# SCH_wifi-temp-sensor_2024-08-15.net
KiCad netlist of a schematic drawn in EasyEDA
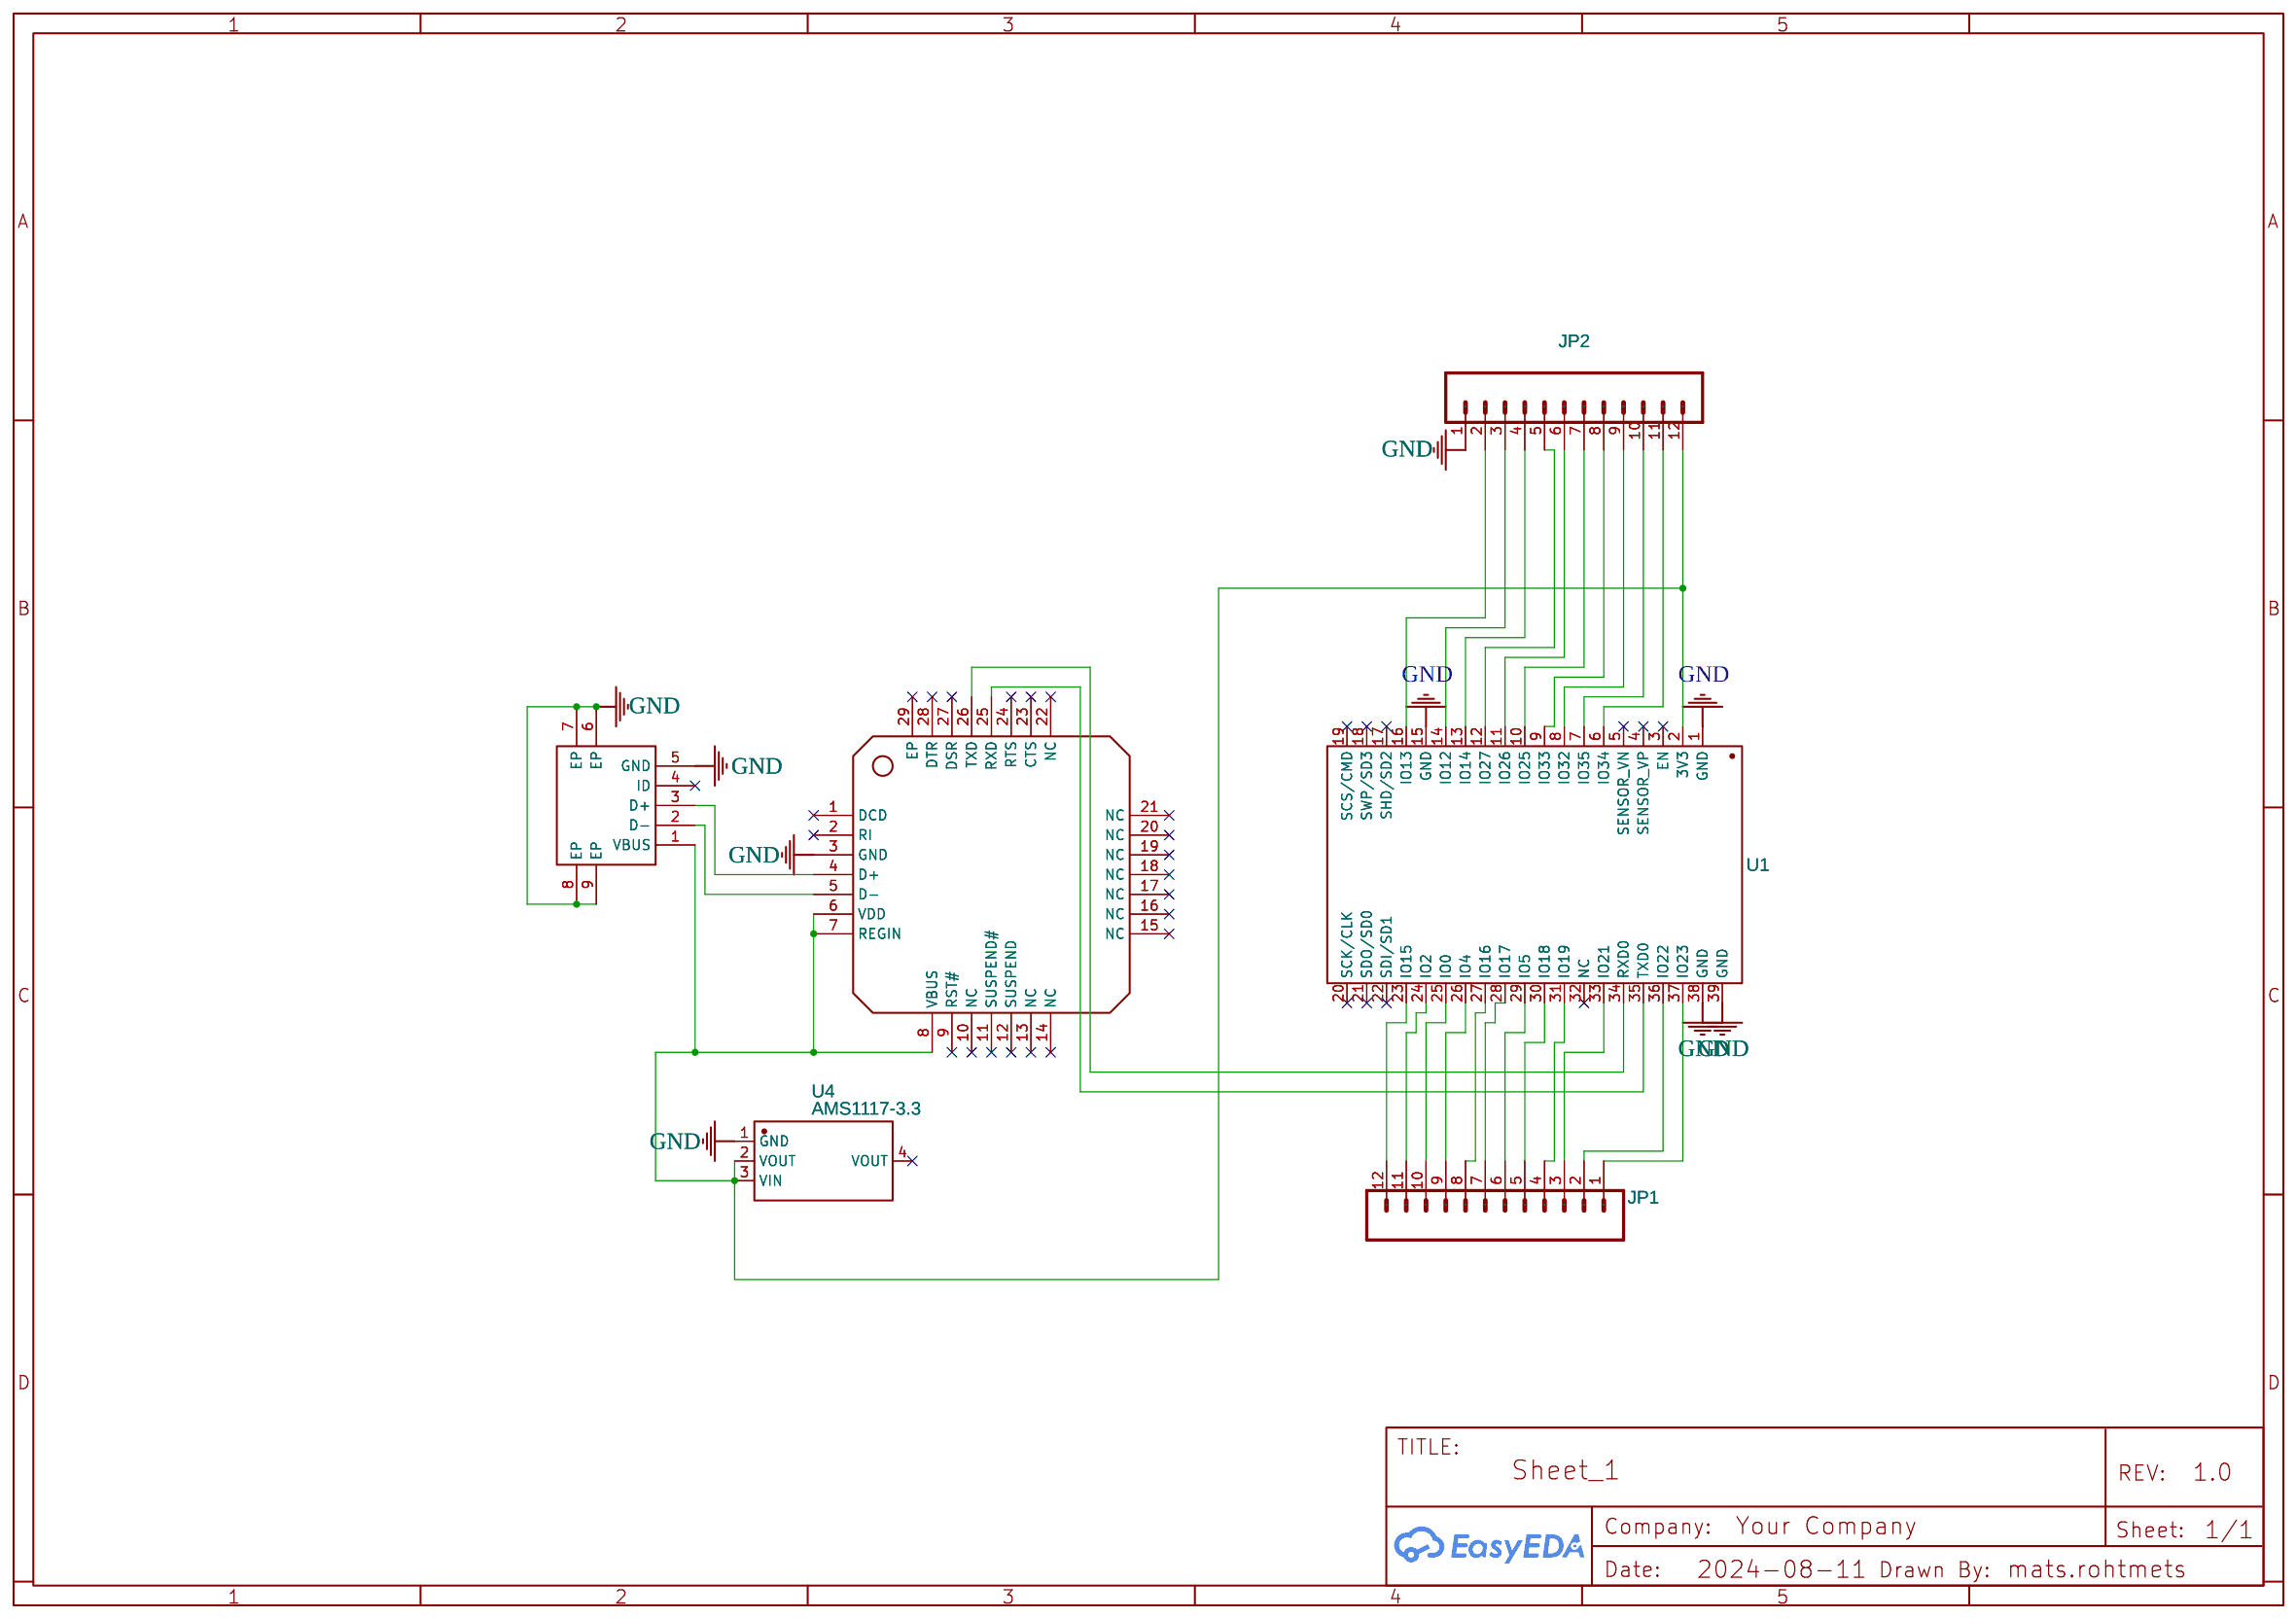
[diagram p0: schematic sheet]

(export (version "E")
  (design (tool "Eeschema 10.0.6"))
  (components
    (comp (ref "JP1")
      (value "M12MACHINE-PIN_LOCK")
      (fields
        (field (name "Manufacturer Part") "HC-PM254-8.5H-1x12PZ")
        (field (name "Manufacturer") "Hong Cheng")
      )
      (libsource (lib "") (part "M12MACHINE-PIN_LOCK"))
    )
    (comp (ref "JP2")
      (value "M12MACHINE-PIN_LOCK")
      (fields
        (field (name "Manufacturer Part") "HC-PM254-8.5H-1x12PZ")
        (field (name "Manufacturer") "Hong Cheng")
      )
      (libsource (lib "") (part "M12MACHINE-PIN_LOCK_1"))
    )
    (comp (ref "U1")
      (value "ESP32-WROOM-32")
      (fields
        (field (name "Manufacturer Part") "ESP32-WROOM-32-N4")
        (field (name "Manufacturer") "ESPRESSIF(乐鑫)")
      )
      (libsource (lib "") (part "ESP32-WROOM-32"))
    )
    (comp (ref "U3")
      (value "CP2102-GMR")
      (fields (field (name "Manufacturer") "SKYWORKS/SILICON LABS(芯科)"))
      (libsource (lib "") (part "CP2102-GMR"))
    )
    (comp (ref "U4")
      (value "AMS1117-3.3")
      (fields (field (name "Manufacturer") "AMS"))
      (libsource (lib "") (part "AMS1117-3.3"))
    )
    (comp (ref "USB1")
      (value "MICRO 7.2JB")
      (fields (field (name "Manufacturer") "SHOU HAN(首韩)"))
      (libsource (lib "") (part "MICRO 7.2JB"))
    )
  )
  (nets
    (net (code "1") (name "GND") (class "Default")
      (node (ref "JP2") (pin "1") (pinfunction "1_1") (pintype "bidirectional"))
      (node (ref "U1") (pin "1") (pinfunction "GND_1") (pintype "unspecified"))
      (node (ref "U1") (pin "15") (pinfunction "GND_15") (pintype "unspecified"))
      (node (ref "U1") (pin "38") (pinfunction "GND_38") (pintype "unspecified"))
      (node (ref "U1") (pin "39") (pinfunction "GND_39") (pintype "unspecified"))
      (node (ref "U3") (pin "3") (pinfunction "GND_3") (pintype "unspecified"))
      (node (ref "U4") (pin "1") (pinfunction "GND_1") (pintype "unspecified"))
      (node (ref "USB1") (pin "5") (pinfunction "GND_5") (pintype "unspecified"))
      (node (ref "USB1") (pin "6") (pinfunction "EP_6") (pintype "unspecified"))
      (node (ref "USB1") (pin "7") (pinfunction "EP_7") (pintype "unspecified"))
      (node (ref "USB1") (pin "8") (pinfunction "EP_8") (pintype "unspecified"))
      (node (ref "USB1") (pin "9") (pinfunction "EP_9") (pintype "unspecified"))
    )
    (net (code "2") (name "Net-(U1-3V3)") (class "Default")
      (node (ref "JP2") (pin "12") (pinfunction "12_12") (pintype "bidirectional"))
      (node (ref "U1") (pin "2") (pinfunction "3V3_2") (pintype "unspecified"))
      (node (ref "U3") (pin "6") (pinfunction "VDD_6") (pintype "unspecified"))
      (node (ref "U3") (pin "7") (pinfunction "REGIN_7") (pintype "unspecified"))
      (node (ref "U3") (pin "8") (pinfunction "VBUS_8") (pintype "unspecified"))
      (node (ref "U4") (pin "2") (pinfunction "VOUT_2") (pintype "unspecified"))
      (node (ref "U4") (pin "3") (pinfunction "VIN_3") (pintype "unspecified"))
      (node (ref "USB1") (pin "1") (pinfunction "VBUS_1") (pintype "unspecified"))
    )
    (net (code "3") (name "Net-(U1-IO0)") (class "Default")
      (node (ref "JP1") (pin "10") (pinfunction "10_10") (pintype "bidirectional"))
      (node (ref "U1") (pin "25") (pinfunction "IO0_25") (pintype "unspecified"))
    )
    (net (code "4") (name "Net-(U1-IO2)") (class "Default")
      (node (ref "JP1") (pin "11") (pinfunction "11_11") (pintype "bidirectional"))
      (node (ref "U1") (pin "24") (pinfunction "IO2_24") (pintype "unspecified"))
    )
    (net (code "5") (name "Net-(U1-IO4)") (class "Default")
      (node (ref "JP1") (pin "9") (pinfunction "9_9") (pintype "bidirectional"))
      (node (ref "U1") (pin "26") (pinfunction "IO4_26") (pintype "unspecified"))
    )
    (net (code "6") (name "Net-(U1-IO5)") (class "Default")
      (node (ref "JP1") (pin "6") (pinfunction "6_6") (pintype "bidirectional"))
      (node (ref "U1") (pin "29") (pinfunction "IO5_29") (pintype "unspecified"))
    )
    (net (code "7") (name "Net-(U1-IO12)") (class "Default")
      (node (ref "JP2") (pin "3") (pinfunction "3_3") (pintype "bidirectional"))
      (node (ref "U1") (pin "14") (pinfunction "IO12_14") (pintype "unspecified"))
    )
    (net (code "8") (name "Net-(U1-IO13)") (class "Default")
      (node (ref "JP2") (pin "2") (pinfunction "2_2") (pintype "bidirectional"))
      (node (ref "U1") (pin "16") (pinfunction "IO13_16") (pintype "unspecified"))
    )
    (net (code "9") (name "Net-(U1-IO14)") (class "Default")
      (node (ref "JP2") (pin "4") (pinfunction "4_4") (pintype "bidirectional"))
      (node (ref "U1") (pin "13") (pinfunction "IO14_13") (pintype "unspecified"))
    )
    (net (code "10") (name "Net-(U1-IO15)") (class "Default")
      (node (ref "JP1") (pin "12") (pinfunction "12_12") (pintype "bidirectional"))
      (node (ref "U1") (pin "23") (pinfunction "IO15_23") (pintype "unspecified"))
    )
    (net (code "11") (name "Net-(U1-IO16)") (class "Default")
      (node (ref "JP1") (pin "8") (pinfunction "8_8") (pintype "bidirectional"))
      (node (ref "U1") (pin "27") (pinfunction "IO16_27") (pintype "unspecified"))
    )
    (net (code "12") (name "Net-(U1-IO17)") (class "Default")
      (node (ref "JP1") (pin "7") (pinfunction "7_7") (pintype "bidirectional"))
      (node (ref "U1") (pin "28") (pinfunction "IO17_28") (pintype "unspecified"))
    )
    (net (code "13") (name "Net-(U1-IO18)") (class "Default")
      (node (ref "JP1") (pin "5") (pinfunction "5_5") (pintype "bidirectional"))
      (node (ref "U1") (pin "30") (pinfunction "IO18_30") (pintype "unspecified"))
    )
    (net (code "14") (name "Net-(U1-IO19)") (class "Default")
      (node (ref "JP1") (pin "4") (pinfunction "4_4") (pintype "bidirectional"))
      (node (ref "U1") (pin "31") (pinfunction "IO19_31") (pintype "unspecified"))
    )
    (net (code "15") (name "Net-(U1-IO21)") (class "Default")
      (node (ref "JP1") (pin "3") (pinfunction "3_3") (pintype "bidirectional"))
      (node (ref "U1") (pin "33") (pinfunction "IO21_33") (pintype "unspecified"))
    )
    (net (code "16") (name "Net-(U1-IO22)") (class "Default")
      (node (ref "JP1") (pin "2") (pinfunction "2_2") (pintype "bidirectional"))
      (node (ref "U1") (pin "36") (pinfunction "IO22_36") (pintype "unspecified"))
    )
    (net (code "17") (name "Net-(U1-IO23)") (class "Default")
      (node (ref "JP1") (pin "1") (pinfunction "1_1") (pintype "bidirectional"))
      (node (ref "U1") (pin "37") (pinfunction "IO23_37") (pintype "unspecified"))
    )
    (net (code "18") (name "Net-(U1-IO25)") (class "Default")
      (node (ref "JP2") (pin "7") (pinfunction "7_7") (pintype "bidirectional"))
      (node (ref "U1") (pin "10") (pinfunction "IO25_10") (pintype "unspecified"))
    )
    (net (code "19") (name "Net-(U1-IO26)") (class "Default")
      (node (ref "JP2") (pin "6") (pinfunction "6_6") (pintype "bidirectional"))
      (node (ref "U1") (pin "11") (pinfunction "IO26_11") (pintype "unspecified"))
    )
    (net (code "20") (name "Net-(U1-IO27)") (class "Default")
      (node (ref "JP2") (pin "5") (pinfunction "5_5") (pintype "bidirectional"))
      (node (ref "U1") (pin "12") (pinfunction "IO27_12") (pintype "unspecified"))
    )
    (net (code "21") (name "Net-(U1-IO32)") (class "Default")
      (node (ref "JP2") (pin "9") (pinfunction "9_9") (pintype "bidirectional"))
      (node (ref "U1") (pin "8") (pinfunction "IO32_8") (pintype "unspecified"))
    )
    (net (code "22") (name "Net-(U1-IO33)") (class "Default")
      (node (ref "JP2") (pin "8") (pinfunction "8_8") (pintype "bidirectional"))
      (node (ref "U1") (pin "9") (pinfunction "IO33_9") (pintype "unspecified"))
    )
    (net (code "23") (name "Net-(U1-IO34)") (class "Default")
      (node (ref "JP2") (pin "11") (pinfunction "11_11") (pintype "bidirectional"))
      (node (ref "U1") (pin "6") (pinfunction "IO34_6") (pintype "unspecified"))
    )
    (net (code "24") (name "Net-(U1-IO35)") (class "Default")
      (node (ref "JP2") (pin "10") (pinfunction "10_10") (pintype "bidirectional"))
      (node (ref "U1") (pin "7") (pinfunction "IO35_7") (pintype "unspecified"))
    )
    (net (code "25") (name "Net-(U1-RXD0)") (class "Default")
      (node (ref "U1") (pin "34") (pinfunction "RXD0_34") (pintype "unspecified"))
      (node (ref "U3") (pin "26") (pinfunction "TXD_26") (pintype "unspecified"))
    )
    (net (code "26") (name "Net-(U1-TXD0)") (class "Default")
      (node (ref "U1") (pin "35") (pinfunction "TXD0_35") (pintype "unspecified"))
      (node (ref "U3") (pin "25") (pinfunction "RXD_25") (pintype "unspecified"))
    )
    (net (code "27") (name "Net-(U3-D+)") (class "Default")
      (node (ref "U3") (pin "4") (pinfunction "D+_4") (pintype "unspecified"))
      (node (ref "USB1") (pin "3") (pinfunction "D+_3") (pintype "unspecified"))
    )
    (net (code "28") (name "Net-(U3-D-)") (class "Default")
      (node (ref "U3") (pin "5") (pinfunction "D-_5") (pintype "unspecified"))
      (node (ref "USB1") (pin "2") (pinfunction "D-_2") (pintype "unspecified"))
    )
    (net (code "29") (name "unconnected-(U1-EN-Pad3)") (class "Default")
      (node (ref "U1") (pin "3") (pinfunction "EN_3") (pintype "unspecified+no_connect"))
    )
    (net (code "30") (name "unconnected-(U1-NC-Pad32)") (class "Default")
      (node (ref "U1") (pin "32") (pinfunction "NC_32") (pintype "unspecified+no_connect"))
    )
    (net (code "31") (name "unconnected-(U1-SCK{slash}CLK-Pad20)") (class "Default")
      (node (ref "U1") (pin "20") (pinfunction "SCK/CLK_20") (pintype "unspecified+no_connect"))
    )
    (net (code "32") (name "unconnected-(U1-SCS{slash}CMD-Pad19)") (class "Default")
      (node (ref "U1") (pin "19") (pinfunction "SCS/CMD_19") (pintype "unspecified+no_connect"))
    )
    (net (code "33") (name "unconnected-(U1-SDI{slash}SD1-Pad22)") (class "Default")
      (node (ref "U1") (pin "22") (pinfunction "SDI/SD1_22") (pintype "unspecified+no_connect"))
    )
    (net (code "34") (name "unconnected-(U1-SDO{slash}SD0-Pad21)") (class "Default")
      (node (ref "U1") (pin "21") (pinfunction "SDO/SD0_21") (pintype "unspecified+no_connect"))
    )
    (net (code "35") (name "unconnected-(U1-SENSOR_VN-Pad5)") (class "Default")
      (node (ref "U1") (pin "5") (pinfunction "SENSOR_VN_5") (pintype "unspecified+no_connect"))
    )
    (net (code "36") (name "unconnected-(U1-SENSOR_VP-Pad4)") (class "Default")
      (node (ref "U1") (pin "4") (pinfunction "SENSOR_VP_4") (pintype "unspecified+no_connect"))
    )
    (net (code "37") (name "unconnected-(U1-SHD{slash}SD2-Pad17)") (class "Default")
      (node (ref "U1") (pin "17") (pinfunction "SHD/SD2_17") (pintype "unspecified+no_connect"))
    )
    (net (code "38") (name "unconnected-(U1-SWP{slash}SD3-Pad18)") (class "Default")
      (node (ref "U1") (pin "18") (pinfunction "SWP/SD3_18") (pintype "unspecified+no_connect"))
    )
    (net (code "39") (name "unconnected-(U3-CTS-Pad23)") (class "Default")
      (node (ref "U3") (pin "23") (pinfunction "CTS_23") (pintype "unspecified+no_connect"))
    )
    (net (code "40") (name "unconnected-(U3-DCD-Pad1)") (class "Default")
      (node (ref "U3") (pin "1") (pinfunction "DCD_1") (pintype "unspecified+no_connect"))
    )
    (net (code "41") (name "unconnected-(U3-DSR-Pad27)") (class "Default")
      (node (ref "U3") (pin "27") (pinfunction "DSR_27") (pintype "unspecified+no_connect"))
    )
    (net (code "42") (name "unconnected-(U3-DTR-Pad28)") (class "Default")
      (node (ref "U3") (pin "28") (pinfunction "DTR_28") (pintype "unspecified+no_connect"))
    )
    (net (code "43") (name "unconnected-(U3-EP-Pad29)") (class "Default")
      (node (ref "U3") (pin "29") (pinfunction "EP_29") (pintype "unspecified+no_connect"))
    )
    (net (code "44") (name "unconnected-(U3-NC-Pad10)") (class "Default")
      (node (ref "U3") (pin "10") (pinfunction "NC_10") (pintype "unspecified+no_connect"))
    )
    (net (code "45") (name "unconnected-(U3-NC-Pad13)") (class "Default")
      (node (ref "U3") (pin "13") (pinfunction "NC_13") (pintype "unspecified+no_connect"))
    )
    (net (code "46") (name "unconnected-(U3-NC-Pad14)") (class "Default")
      (node (ref "U3") (pin "14") (pinfunction "NC_14") (pintype "unspecified+no_connect"))
    )
    (net (code "47") (name "unconnected-(U3-NC-Pad15)") (class "Default")
      (node (ref "U3") (pin "15") (pinfunction "NC_15") (pintype "unspecified+no_connect"))
    )
    (net (code "48") (name "unconnected-(U3-NC-Pad16)") (class "Default")
      (node (ref "U3") (pin "16") (pinfunction "NC_16") (pintype "unspecified+no_connect"))
    )
    (net (code "49") (name "unconnected-(U3-NC-Pad17)") (class "Default")
      (node (ref "U3") (pin "17") (pinfunction "NC_17") (pintype "unspecified+no_connect"))
    )
    (net (code "50") (name "unconnected-(U3-NC-Pad18)") (class "Default")
      (node (ref "U3") (pin "18") (pinfunction "NC_18") (pintype "unspecified+no_connect"))
    )
    (net (code "51") (name "unconnected-(U3-NC-Pad19)") (class "Default")
      (node (ref "U3") (pin "19") (pinfunction "NC_19") (pintype "unspecified+no_connect"))
    )
    (net (code "52") (name "unconnected-(U3-NC-Pad20)") (class "Default")
      (node (ref "U3") (pin "20") (pinfunction "NC_20") (pintype "unspecified+no_connect"))
    )
    (net (code "53") (name "unconnected-(U3-NC-Pad21)") (class "Default")
      (node (ref "U3") (pin "21") (pinfunction "NC_21") (pintype "unspecified+no_connect"))
    )
    (net (code "54") (name "unconnected-(U3-NC-Pad22)") (class "Default")
      (node (ref "U3") (pin "22") (pinfunction "NC_22") (pintype "unspecified+no_connect"))
    )
    (net (code "55") (name "unconnected-(U3-RI-Pad2)") (class "Default")
      (node (ref "U3") (pin "2") (pinfunction "RI_2") (pintype "unspecified+no_connect"))
    )
    (net (code "56") (name "unconnected-(U3-RST#-Pad9)") (class "Default")
      (node (ref "U3") (pin "9") (pinfunction "RST#_9") (pintype "unspecified+no_connect"))
    )
    (net (code "57") (name "unconnected-(U3-RTS-Pad24)") (class "Default")
      (node (ref "U3") (pin "24") (pinfunction "RTS_24") (pintype "unspecified+no_connect"))
    )
    (net (code "58") (name "unconnected-(U3-SUSPEND#-Pad11)") (class "Default")
      (node (ref "U3") (pin "11") (pinfunction "SUSPEND#_11") (pintype "unspecified+no_connect"))
    )
    (net (code "59") (name "unconnected-(U3-SUSPEND-Pad12)") (class "Default")
      (node (ref "U3") (pin "12") (pinfunction "SUSPEND_12") (pintype "unspecified+no_connect"))
    )
    (net (code "60") (name "unconnected-(U4-VOUT-Pad4)") (class "Default")
      (node (ref "U4") (pin "4") (pinfunction "VOUT_4") (pintype "unspecified+no_connect"))
    )
    (net (code "61") (name "unconnected-(USB1-ID-Pad4)") (class "Default")
      (node (ref "USB1") (pin "4") (pinfunction "ID_4") (pintype "unspecified+no_connect"))
    )
  )
)
